# Connectors.net
KiCad netlist of a schematic drawn in Altium Designer
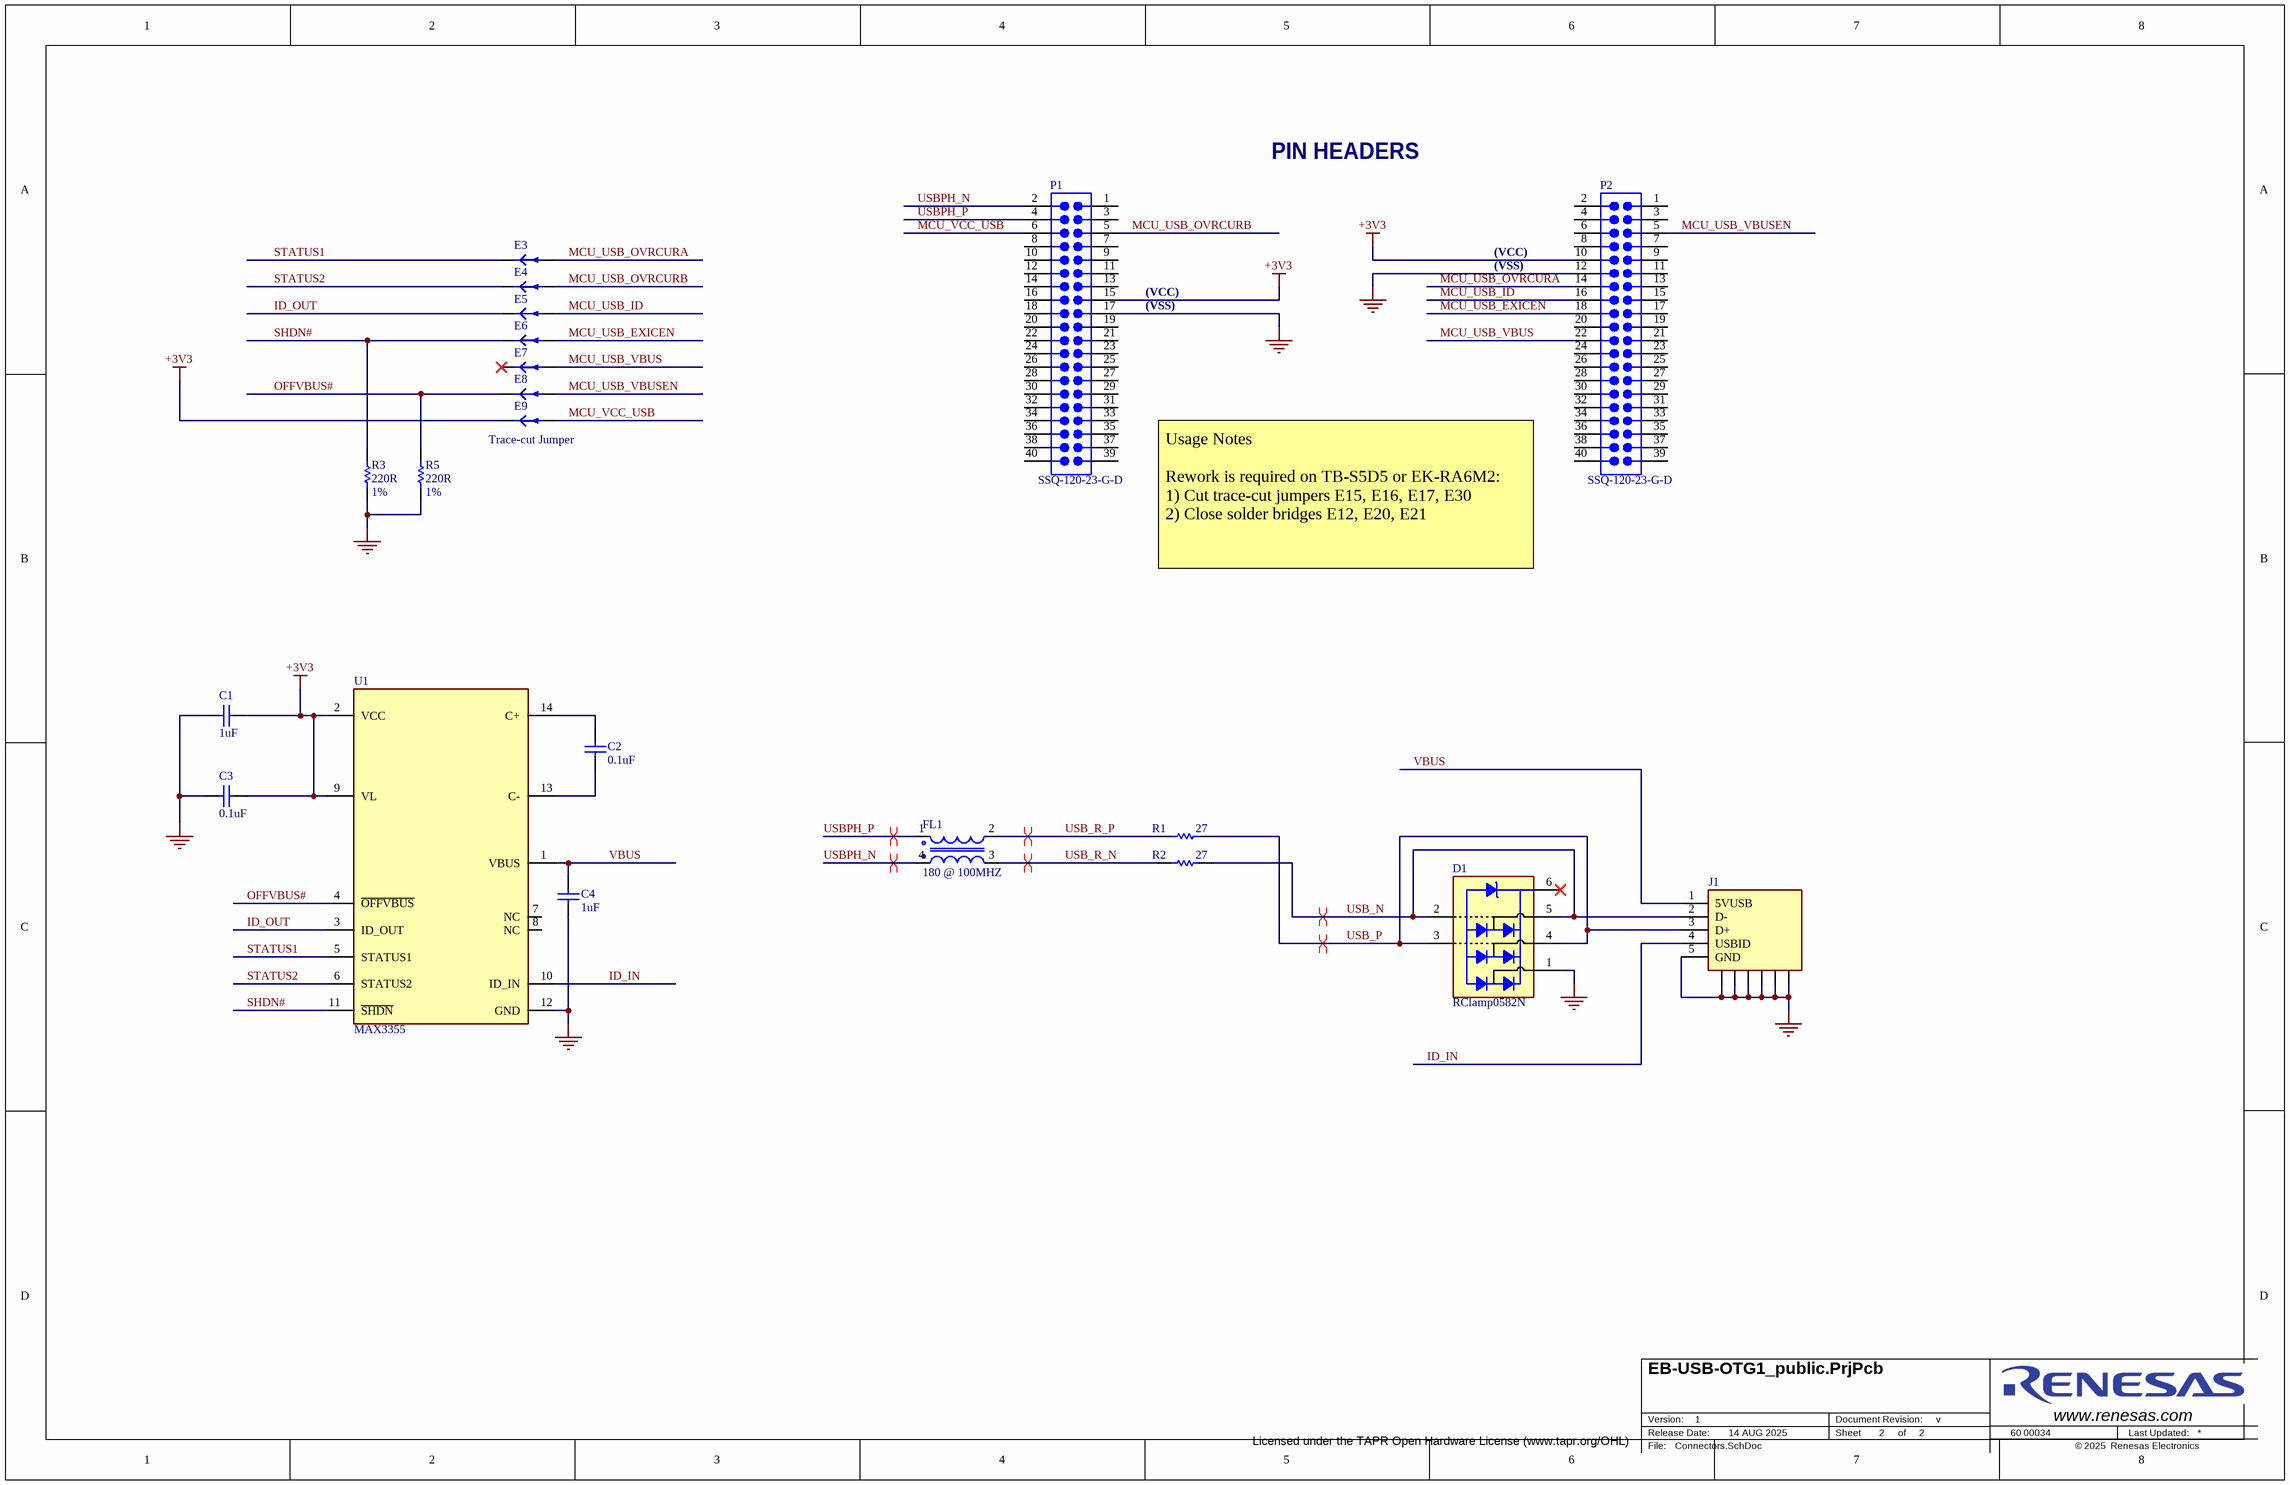
[diagram p0: Connectors.SchDoc]

(export (version "E")
  (design (tool "Eeschema 10.0.6"))
  (components
    (comp (ref "C1")
      (value "CAP-000074-01")
      (footprint "CAPC0603-01")
      (description "Ceramic Chip Capacitor 0603 1uF 50V")
      (fields
        (field (name "MANUFACTURER") "Taiyo Yuden")
        (field (name "MFG PART NUMBER") "UMK107BJ105KA-T")
        (field (name "CAPACITANCE") "1uF")
      )
      (libsource (lib "Capacitors") (part "CAP-000074-01"))
    )
    (comp (ref "C2")
      (value "CAP-000029-01")
      (footprint "CAPC0603-01")
      (description "Ceramic Chip Capacitor 0603 0.1uF 50V")
      (fields
        (field (name "MANUFACTURER") "Samsung")
        (field (name "MFG PART NUMBER") "CL10B104KB8NNNC")
        (field (name "CAPACITANCE") "0.1uF")
      )
      (libsource (lib "Capacitors") (part "CAP-000029-01"))
    )
    (comp (ref "C3")
      (value "CAP-000029-01")
      (footprint "CAPC0603-01")
      (description "Ceramic Chip Capacitor 0603 0.1uF 50V")
      (fields
        (field (name "MANUFACTURER") "Samsung")
        (field (name "MFG PART NUMBER") "CL10B104KB8NNNC")
        (field (name "CAPACITANCE") "0.1uF")
      )
      (libsource (lib "Capacitors") (part "CAP-000029-01"))
    )
    (comp (ref "C4")
      (value "CAP-000074-01")
      (footprint "CAPC0603-01")
      (description "Ceramic Chip Capacitor 0603 1uF 50V")
      (fields
        (field (name "MANUFACTURER") "Taiyo Yuden")
        (field (name "MFG PART NUMBER") "UMK107BJ105KA-T")
        (field (name "CAPACITANCE") "1uF")
      )
      (libsource (lib "Capacitors") (part "CAP-000074-01"))
    )
    (comp (ref "D1")
      (value "DIO-100005-01")
      (footprint "SEMTECH_SLP1210N6")
      (description "Semtech TVS Diode Array for USB")
      (fields
        (field (name "MANUFACTURER") "Semtech")
        (field (name "MFG PART NUMBER") "RClamp0582N.TCT")
        (field (name "DISPLAY NAME") "RClamp0582N")
      )
      (libsource (lib "Semiconductors") (part "DIO-100005-01"))
    )
    (comp (ref "E3")
      (value "TIE-100001-01")
      (footprint "TraceCut0805")
      (description "Trace-Cut Jumper.  Pads on PCB with Trace Between for Cutting to isolate")
      (libsource (lib "Misc") (part "TIE-100001-01"))
    )
    (comp (ref "E4")
      (value "TIE-100001-01")
      (footprint "TraceCut0805")
      (description "Trace-Cut Jumper.  Pads on PCB with Trace Between for Cutting to isolate")
      (libsource (lib "Misc") (part "TIE-100001-01"))
    )
    (comp (ref "E5")
      (value "TIE-100001-01")
      (footprint "TraceCut0805")
      (description "Trace-Cut Jumper.  Pads on PCB with Trace Between for Cutting to isolate")
      (libsource (lib "Misc") (part "TIE-100001-01"))
    )
    (comp (ref "E6")
      (value "TIE-100001-01")
      (footprint "TraceCut0805")
      (description "Trace-Cut Jumper.  Pads on PCB with Trace Between for Cutting to isolate")
      (libsource (lib "Misc") (part "TIE-100001-01"))
    )
    (comp (ref "E7")
      (value "TIE-100001-01")
      (footprint "TraceCut0805")
      (description "Trace-Cut Jumper.  Pads on PCB with Trace Between for Cutting to isolate")
      (libsource (lib "Misc") (part "TIE-100001-01"))
    )
    (comp (ref "E8")
      (value "TIE-100001-01")
      (footprint "TraceCut0805")
      (description "Trace-Cut Jumper.  Pads on PCB with Trace Between for Cutting to isolate")
      (libsource (lib "Misc") (part "TIE-100001-01"))
    )
    (comp (ref "E9")
      (value "TIE-100001-01")
      (footprint "TraceCut0805")
      (description "Trace-Cut Jumper.  Pads on PCB with Trace Between for Cutting to isolate")
      (fields (field (name "DISPLAY_NAME") "Trace-cut Jumper"))
      (libsource (lib "Misc") (part "TIE-100001-01"))
    )
    (comp (ref "FL1")
      (value "IND-100014-01")
      (footprint "MURATA_FL0805")
      (description "Common Mode Filter Inductor, 180 ohm CM @ 100MHz, 0805")
      (fields
        (field (name "MANUFACTURER") "Murata")
        (field (name "MFG PART NUMBER") "DLW21SN181SQ2")
        (field (name "RESISTANCE") "180 @ 100MHZ")
      )
      (libsource (lib "Misc") (part "IND-100014-01"))
    )
    (comp (ref "J1")
      (value "CON-100013-01")
      (footprint "MOLEX_47589-0001")
      (description "USB Micro AB 2.0 Female 5 Pin Right Angle Molex")
      (fields (field (name "MANUFACTURER") "Molex") (field (name "MFG PART NUMBER") "47589-0001"))
      (libsource (lib "Connectors") (part "CON-100013-01"))
    )
    (comp (ref "P1")
      (value "CON-100032-01")
      (footprint "SAMTEC_SSQ-120-23-x-D")
      (description "SAMTEC Female Header 0.1\" pitch 40pos 2x20, 10mm pins, gold flash tail")
      (fields
        (field (name "MANUFACTURER") "Samtec")
        (field (name "MFG PART NUMBER") "SSQ-120-23-G-D")
        (field (name "PN") "SSQ-120-23-G-D")
      )
      (libsource (lib "Connectors") (part "CON-100032-01"))
    )
    (comp (ref "P2")
      (value "CON-100032-01")
      (footprint "SAMTEC_SSQ-120-23-x-D")
      (description "SAMTEC Female Header 0.1\" pitch 40pos 2x20, 10mm pins, gold flash tail")
      (fields
        (field (name "MANUFACTURER") "Samtec")
        (field (name "MFG PART NUMBER") "SSQ-120-23-G-D")
        (field (name "PN") "SSQ-120-23-G-D")
      )
      (libsource (lib "Connectors") (part "CON-100032-01"))
    )
    (comp (ref "R1")
      (value "RES-100084-01")
      (footprint "RESC0603-01")
      (description "Chip Resistor Thick Film 0603 27R0 1% 1/10W")
      (fields
        (field (name "MANUFACTURER") "Yageo")
        (field (name "MFG PART NUMBER") "RC0603FR-0727RL")
        (field (name "RESISTANCE") "27")
      )
      (libsource (lib "Resistors") (part "RES-100084-01"))
    )
    (comp (ref "R2")
      (value "RES-100084-01")
      (footprint "RESC0603-01")
      (description "Chip Resistor Thick Film 0603 27R0 1% 1/10W")
      (fields
        (field (name "MANUFACTURER") "Yageo")
        (field (name "MFG PART NUMBER") "RC0603FR-0727RL")
        (field (name "RESISTANCE") "27")
      )
      (libsource (lib "Resistors") (part "RES-100084-01"))
    )
    (comp (ref "R3")
      (value "RES-100092-01")
      (footprint "RESC0603-01")
      (description "Chip Resistor Thick Film 0603 220 ohm 1% 1/10W")
      (fields
        (field (name "MANUFACTURER") "Yageo")
        (field (name "MFG PART NUMBER") "RC0603FR-07220RL")
        (field (name "RESISTANCE") "220R")
        (field (name "TOLERANCE") "1%")
      )
      (libsource (lib "Resistors") (part "RES-100092-01"))
    )
    (comp (ref "R5")
      (value "RES-100092-01")
      (footprint "RESC0603-01")
      (description "Chip Resistor Thick Film 0603 220 ohm 1% 1/10W")
      (fields
        (field (name "MANUFACTURER") "Yageo")
        (field (name "MFG PART NUMBER") "RC0603FR-07220RL")
        (field (name "RESISTANCE") "220R")
        (field (name "TOLERANCE") "1%")
      )
      (libsource (lib "Resistors") (part "RES-100092-01"))
    )
    (comp (ref "U1")
      (value "ICN-110015-01")
      (footprint "MAXIM_TSSOP-14")
      (description "USB OTG Charge Pump")
      (fields
        (field (name "MANUFACTURER") "Maxim")
        (field (name "MFG PART NUMBER") "MAX3355EEUD")
        (field (name "DISPLAY NAME") "MAX3355")
      )
      (libsource (lib "IC_Power") (part "ICN-110015-01"))
    )
  )
  (nets
    (net (code "1") (name "+3V3") (class "Default")
      (node (ref "C1") (pin "1") (pinfunction "1_1") (pintype "passive"))
      (node (ref "C3") (pin "1") (pinfunction "1_1") (pintype "passive"))
      (node (ref "E9") (pin "1") (pinfunction "A_1") (pintype "passive"))
      (node (ref "P1") (pin "15") (pinfunction "15_15") (pintype "passive"))
      (node (ref "P2") (pin "10") (pinfunction "10_10") (pintype "passive"))
      (node (ref "U1") (pin "2") (pinfunction "VCC_2") (pintype "power_in"))
      (node (ref "U1") (pin "9") (pinfunction "VL_9") (pintype "passive"))
    )
    (net (code "2") (name "/ID_IN") (class "Default")
      (node (ref "J1") (pin "4") (pinfunction "USBID_4") (pintype "passive"))
      (node (ref "U1") (pin "10") (pinfunction "ID_IN_10") (pintype "passive"))
    )
    (net (code "3") (name "/ID_OUT") (class "Default")
      (node (ref "E5") (pin "1") (pinfunction "A_1") (pintype "passive"))
      (node (ref "U1") (pin "3") (pinfunction "ID_OUT_3") (pintype "passive"))
    )
    (net (code "4") (name "/MCU_USB_EXICEN") (class "Default")
      (node (ref "E6") (pin "2") (pinfunction "A_2") (pintype "passive"))
      (node (ref "P2") (pin "18") (pinfunction "18_18") (pintype "passive"))
    )
    (net (code "5") (name "/MCU_USB_ID") (class "Default")
      (node (ref "E5") (pin "2") (pinfunction "A_2") (pintype "passive"))
      (node (ref "P2") (pin "16") (pinfunction "16_16") (pintype "passive"))
    )
    (net (code "6") (name "/MCU_USB_OVRCURA") (class "Default")
      (node (ref "E3") (pin "2") (pinfunction "A_2") (pintype "passive"))
      (node (ref "P2") (pin "14") (pinfunction "14_14") (pintype "passive"))
    )
    (net (code "7") (name "/MCU_USB_OVRCURB") (class "Default")
      (node (ref "E4") (pin "2") (pinfunction "A_2") (pintype "passive"))
      (node (ref "P1") (pin "5") (pinfunction "5_5") (pintype "passive"))
    )
    (net (code "8") (name "/MCU_USB_VBUS") (class "Default")
      (node (ref "E7") (pin "2") (pinfunction "A_2") (pintype "passive"))
      (node (ref "P2") (pin "22") (pinfunction "22_22") (pintype "passive"))
    )
    (net (code "9") (name "/MCU_USB_VBUSEN") (class "Default")
      (node (ref "E8") (pin "2") (pinfunction "A_2") (pintype "passive"))
      (node (ref "P2") (pin "5") (pinfunction "5_5") (pintype "passive"))
    )
    (net (code "10") (name "/MCU_VCC_USB") (class "Default")
      (node (ref "E9") (pin "2") (pinfunction "A_2") (pintype "passive"))
      (node (ref "P1") (pin "6") (pinfunction "6_6") (pintype "passive"))
    )
    (net (code "11") (name "/OFFVBUS#") (class "Default")
      (node (ref "E8") (pin "1") (pinfunction "A_1") (pintype "passive"))
      (node (ref "R5") (pin "2") (pinfunction "2_2") (pintype "passive"))
      (node (ref "U1") (pin "4") (pinfunction "~{OFFVBUS}_4") (pintype "power_in"))
    )
    (net (code "12") (name "/SHDN#") (class "Default")
      (node (ref "E6") (pin "1") (pinfunction "A_1") (pintype "passive"))
      (node (ref "R3") (pin "2") (pinfunction "2_2") (pintype "passive"))
      (node (ref "U1") (pin "11") (pinfunction "~{SHDN}_11") (pintype "passive"))
    )
    (net (code "13") (name "/STATUS1") (class "Default")
      (node (ref "E3") (pin "1") (pinfunction "A_1") (pintype "passive"))
      (node (ref "U1") (pin "5") (pinfunction "STATUS1_5") (pintype "passive"))
    )
    (net (code "14") (name "/STATUS2") (class "Default")
      (node (ref "E4") (pin "1") (pinfunction "A_1") (pintype "passive"))
      (node (ref "U1") (pin "6") (pinfunction "STATUS2_6") (pintype "passive"))
    )
    (net (code "15") (name "/USBPH_N") (class "Default")
      (node (ref "FL1") (pin "4") (pinfunction "4_4") (pintype "passive"))
      (node (ref "P1") (pin "2") (pinfunction "2_2") (pintype "passive"))
    )
    (net (code "16") (name "/USBPH_P") (class "Default")
      (node (ref "FL1") (pin "1") (pinfunction "1_1") (pintype "passive"))
      (node (ref "P1") (pin "4") (pinfunction "4_4") (pintype "passive"))
    )
    (net (code "17") (name "/USB_N") (class "Default")
      (node (ref "D1") (pin "2") (pinfunction "NC_2") (pintype "passive"))
      (node (ref "D1") (pin "5") (pinfunction "5_5") (pintype "passive"))
      (node (ref "J1") (pin "2") (pinfunction "D-_2") (pintype "passive"))
      (node (ref "R2") (pin "2") (pinfunction "2_2") (pintype "passive"))
    )
    (net (code "18") (name "/USB_P") (class "Default")
      (node (ref "D1") (pin "3") (pinfunction "NC_3") (pintype "passive"))
      (node (ref "D1") (pin "4") (pinfunction "4_4") (pintype "passive"))
      (node (ref "J1") (pin "3") (pinfunction "D+_3") (pintype "passive"))
      (node (ref "R1") (pin "2") (pinfunction "2_2") (pintype "passive"))
    )
    (net (code "19") (name "/USB_R_N") (class "Default")
      (node (ref "FL1") (pin "3") (pinfunction "3_3") (pintype "passive"))
      (node (ref "R2") (pin "1") (pinfunction "1_1") (pintype "passive"))
    )
    (net (code "20") (name "/USB_R_P") (class "Default")
      (node (ref "FL1") (pin "2") (pinfunction "2_2") (pintype "passive"))
      (node (ref "R1") (pin "1") (pinfunction "1_1") (pintype "passive"))
    )
    (net (code "21") (name "/VBUS") (class "Default")
      (node (ref "C4") (pin "2") (pinfunction "2_2") (pintype "passive"))
      (node (ref "J1") (pin "1") (pinfunction "5VUSB_1") (pintype "passive"))
      (node (ref "U1") (pin "1") (pinfunction "VBUS_1") (pintype "power_in"))
    )
    (net (code "22") (name "GND") (class "Default")
      (node (ref "C1") (pin "2") (pinfunction "2_2") (pintype "passive"))
      (node (ref "C3") (pin "2") (pinfunction "2_2") (pintype "passive"))
      (node (ref "C4") (pin "1") (pinfunction "1_1") (pintype "passive"))
      (node (ref "D1") (pin "1") (pinfunction "1_1") (pintype "passive"))
      (node (ref "J1") (pin "5") (pinfunction "GND_5") (pintype "passive"))
      (node (ref "J1") (pin "C1") (pinfunction "C1_C1") (pintype "passive"))
      (node (ref "J1") (pin "C2") (pinfunction "C2_C2") (pintype "passive"))
      (node (ref "J1") (pin "C3") (pinfunction "C3_C3") (pintype "passive"))
      (node (ref "J1") (pin "C4") (pinfunction "C4_C4") (pintype "passive"))
      (node (ref "J1") (pin "C5") (pinfunction "C5_C5") (pintype "passive"))
      (node (ref "J1") (pin "C6") (pinfunction "C6_C6") (pintype "passive"))
      (node (ref "P1") (pin "17") (pinfunction "17_17") (pintype "passive"))
      (node (ref "P2") (pin "12") (pinfunction "12_12") (pintype "passive"))
      (node (ref "R3") (pin "1") (pinfunction "1_1") (pintype "passive"))
      (node (ref "R5") (pin "1") (pinfunction "1_1") (pintype "passive"))
      (node (ref "U1") (pin "12") (pinfunction "GND_12") (pintype "passive"))
    )
    (net (code "23") (name "Net-(U1-C+)") (class "Default")
      (node (ref "C2") (pin "2") (pinfunction "2_2") (pintype "passive"))
      (node (ref "U1") (pin "14") (pinfunction "C+_14") (pintype "passive"))
    )
    (net (code "24") (name "Net-(U1-C-)") (class "Default")
      (node (ref "C2") (pin "1") (pinfunction "1_1") (pintype "passive"))
      (node (ref "U1") (pin "13") (pinfunction "C-_13") (pintype "passive"))
    )
    (net (code "25") (name "unconnected-(D1-Pad6)") (class "Default")
      (node (ref "D1") (pin "6") (pinfunction "6_6") (pintype "passive+no_connect"))
    )
    (net (code "26") (name "unconnected-(E7-A-Pad1)") (class "Default")
      (node (ref "E7") (pin "1") (pinfunction "A_1") (pintype "passive+no_connect"))
    )
    (net (code "27") (name "unconnected-(P1-Pad1)") (class "Default")
      (node (ref "P1") (pin "1") (pinfunction "1_1") (pintype "passive"))
    )
    (net (code "28") (name "unconnected-(P1-Pad3)") (class "Default")
      (node (ref "P1") (pin "3") (pinfunction "3_3") (pintype "passive"))
    )
    (net (code "29") (name "unconnected-(P1-Pad7)") (class "Default")
      (node (ref "P1") (pin "7") (pinfunction "7_7") (pintype "passive"))
    )
    (net (code "30") (name "unconnected-(P1-Pad8)") (class "Default")
      (node (ref "P1") (pin "8") (pinfunction "8_8") (pintype "passive"))
    )
    (net (code "31") (name "unconnected-(P1-Pad9)") (class "Default")
      (node (ref "P1") (pin "9") (pinfunction "9_9") (pintype "passive"))
    )
    (net (code "32") (name "unconnected-(P1-Pad10)") (class "Default")
      (node (ref "P1") (pin "10") (pinfunction "10_10") (pintype "passive"))
    )
    (net (code "33") (name "unconnected-(P1-Pad11)") (class "Default")
      (node (ref "P1") (pin "11") (pinfunction "11_11") (pintype "passive"))
    )
    (net (code "34") (name "unconnected-(P1-Pad12)") (class "Default")
      (node (ref "P1") (pin "12") (pinfunction "12_12") (pintype "passive"))
    )
    (net (code "35") (name "unconnected-(P1-Pad13)") (class "Default")
      (node (ref "P1") (pin "13") (pinfunction "13_13") (pintype "passive"))
    )
    (net (code "36") (name "unconnected-(P1-Pad14)") (class "Default")
      (node (ref "P1") (pin "14") (pinfunction "14_14") (pintype "passive"))
    )
    (net (code "37") (name "unconnected-(P1-Pad16)") (class "Default")
      (node (ref "P1") (pin "16") (pinfunction "16_16") (pintype "passive"))
    )
    (net (code "38") (name "unconnected-(P1-Pad18)") (class "Default")
      (node (ref "P1") (pin "18") (pinfunction "18_18") (pintype "passive"))
    )
    (net (code "39") (name "unconnected-(P1-Pad19)") (class "Default")
      (node (ref "P1") (pin "19") (pinfunction "19_19") (pintype "passive"))
    )
    (net (code "40") (name "unconnected-(P1-Pad20)") (class "Default")
      (node (ref "P1") (pin "20") (pinfunction "20_20") (pintype "passive"))
    )
    (net (code "41") (name "unconnected-(P1-Pad21)") (class "Default")
      (node (ref "P1") (pin "21") (pinfunction "21_21") (pintype "passive"))
    )
    (net (code "42") (name "unconnected-(P1-Pad22)") (class "Default")
      (node (ref "P1") (pin "22") (pinfunction "22_22") (pintype "passive"))
    )
    (net (code "43") (name "unconnected-(P1-Pad23)") (class "Default")
      (node (ref "P1") (pin "23") (pinfunction "23_23") (pintype "passive"))
    )
    (net (code "44") (name "unconnected-(P1-Pad24)") (class "Default")
      (node (ref "P1") (pin "24") (pinfunction "24_24") (pintype "passive"))
    )
    (net (code "45") (name "unconnected-(P1-Pad25)") (class "Default")
      (node (ref "P1") (pin "25") (pinfunction "25_25") (pintype "passive"))
    )
    (net (code "46") (name "unconnected-(P1-Pad26)") (class "Default")
      (node (ref "P1") (pin "26") (pinfunction "26_26") (pintype "passive"))
    )
    (net (code "47") (name "unconnected-(P1-Pad27)") (class "Default")
      (node (ref "P1") (pin "27") (pinfunction "27_27") (pintype "passive"))
    )
    (net (code "48") (name "unconnected-(P1-Pad28)") (class "Default")
      (node (ref "P1") (pin "28") (pinfunction "28_28") (pintype "passive"))
    )
    (net (code "49") (name "unconnected-(P1-Pad29)") (class "Default")
      (node (ref "P1") (pin "29") (pinfunction "29_29") (pintype "passive"))
    )
    (net (code "50") (name "unconnected-(P1-Pad30)") (class "Default")
      (node (ref "P1") (pin "30") (pinfunction "30_30") (pintype "passive"))
    )
    (net (code "51") (name "unconnected-(P1-Pad31)") (class "Default")
      (node (ref "P1") (pin "31") (pinfunction "31_31") (pintype "passive"))
    )
    (net (code "52") (name "unconnected-(P1-Pad32)") (class "Default")
      (node (ref "P1") (pin "32") (pinfunction "32_32") (pintype "passive"))
    )
    (net (code "53") (name "unconnected-(P1-Pad33)") (class "Default")
      (node (ref "P1") (pin "33") (pinfunction "33_33") (pintype "passive"))
    )
    (net (code "54") (name "unconnected-(P1-Pad34)") (class "Default")
      (node (ref "P1") (pin "34") (pinfunction "34_34") (pintype "passive"))
    )
    (net (code "55") (name "unconnected-(P1-Pad35)") (class "Default")
      (node (ref "P1") (pin "35") (pinfunction "35_35") (pintype "passive"))
    )
    (net (code "56") (name "unconnected-(P1-Pad36)") (class "Default")
      (node (ref "P1") (pin "36") (pinfunction "36_36") (pintype "passive"))
    )
    (net (code "57") (name "unconnected-(P1-Pad37)") (class "Default")
      (node (ref "P1") (pin "37") (pinfunction "37_37") (pintype "passive"))
    )
    (net (code "58") (name "unconnected-(P1-Pad38)") (class "Default")
      (node (ref "P1") (pin "38") (pinfunction "38_38") (pintype "passive"))
    )
    (net (code "59") (name "unconnected-(P1-Pad39)") (class "Default")
      (node (ref "P1") (pin "39") (pinfunction "39_39") (pintype "passive"))
    )
    (net (code "60") (name "unconnected-(P1-Pad40)") (class "Default")
      (node (ref "P1") (pin "40") (pinfunction "40_40") (pintype "passive"))
    )
    (net (code "61") (name "unconnected-(P2-Pad1)") (class "Default")
      (node (ref "P2") (pin "1") (pinfunction "1_1") (pintype "passive"))
    )
    (net (code "62") (name "unconnected-(P2-Pad2)") (class "Default")
      (node (ref "P2") (pin "2") (pinfunction "2_2") (pintype "passive"))
    )
    (net (code "63") (name "unconnected-(P2-Pad3)") (class "Default")
      (node (ref "P2") (pin "3") (pinfunction "3_3") (pintype "passive"))
    )
    (net (code "64") (name "unconnected-(P2-Pad4)") (class "Default")
      (node (ref "P2") (pin "4") (pinfunction "4_4") (pintype "passive"))
    )
    (net (code "65") (name "unconnected-(P2-Pad6)") (class "Default")
      (node (ref "P2") (pin "6") (pinfunction "6_6") (pintype "passive"))
    )
    (net (code "66") (name "unconnected-(P2-Pad7)") (class "Default")
      (node (ref "P2") (pin "7") (pinfunction "7_7") (pintype "passive"))
    )
    (net (code "67") (name "unconnected-(P2-Pad8)") (class "Default")
      (node (ref "P2") (pin "8") (pinfunction "8_8") (pintype "passive"))
    )
    (net (code "68") (name "unconnected-(P2-Pad9)") (class "Default")
      (node (ref "P2") (pin "9") (pinfunction "9_9") (pintype "passive"))
    )
    (net (code "69") (name "unconnected-(P2-Pad11)") (class "Default")
      (node (ref "P2") (pin "11") (pinfunction "11_11") (pintype "passive"))
    )
    (net (code "70") (name "unconnected-(P2-Pad13)") (class "Default")
      (node (ref "P2") (pin "13") (pinfunction "13_13") (pintype "passive"))
    )
    (net (code "71") (name "unconnected-(P2-Pad15)") (class "Default")
      (node (ref "P2") (pin "15") (pinfunction "15_15") (pintype "passive"))
    )
    (net (code "72") (name "unconnected-(P2-Pad17)") (class "Default")
      (node (ref "P2") (pin "17") (pinfunction "17_17") (pintype "passive"))
    )
    (net (code "73") (name "unconnected-(P2-Pad19)") (class "Default")
      (node (ref "P2") (pin "19") (pinfunction "19_19") (pintype "passive"))
    )
    (net (code "74") (name "unconnected-(P2-Pad20)") (class "Default")
      (node (ref "P2") (pin "20") (pinfunction "20_20") (pintype "passive"))
    )
    (net (code "75") (name "unconnected-(P2-Pad21)") (class "Default")
      (node (ref "P2") (pin "21") (pinfunction "21_21") (pintype "passive"))
    )
    (net (code "76") (name "unconnected-(P2-Pad23)") (class "Default")
      (node (ref "P2") (pin "23") (pinfunction "23_23") (pintype "passive"))
    )
    (net (code "77") (name "unconnected-(P2-Pad24)") (class "Default")
      (node (ref "P2") (pin "24") (pinfunction "24_24") (pintype "passive"))
    )
    (net (code "78") (name "unconnected-(P2-Pad25)") (class "Default")
      (node (ref "P2") (pin "25") (pinfunction "25_25") (pintype "passive"))
    )
    (net (code "79") (name "unconnected-(P2-Pad26)") (class "Default")
      (node (ref "P2") (pin "26") (pinfunction "26_26") (pintype "passive"))
    )
    (net (code "80") (name "unconnected-(P2-Pad27)") (class "Default")
      (node (ref "P2") (pin "27") (pinfunction "27_27") (pintype "passive"))
    )
    (net (code "81") (name "unconnected-(P2-Pad28)") (class "Default")
      (node (ref "P2") (pin "28") (pinfunction "28_28") (pintype "passive"))
    )
    (net (code "82") (name "unconnected-(P2-Pad29)") (class "Default")
      (node (ref "P2") (pin "29") (pinfunction "29_29") (pintype "passive"))
    )
    (net (code "83") (name "unconnected-(P2-Pad30)") (class "Default")
      (node (ref "P2") (pin "30") (pinfunction "30_30") (pintype "passive"))
    )
    (net (code "84") (name "unconnected-(P2-Pad31)") (class "Default")
      (node (ref "P2") (pin "31") (pinfunction "31_31") (pintype "passive"))
    )
    (net (code "85") (name "unconnected-(P2-Pad32)") (class "Default")
      (node (ref "P2") (pin "32") (pinfunction "32_32") (pintype "passive"))
    )
    (net (code "86") (name "unconnected-(P2-Pad33)") (class "Default")
      (node (ref "P2") (pin "33") (pinfunction "33_33") (pintype "passive"))
    )
    (net (code "87") (name "unconnected-(P2-Pad34)") (class "Default")
      (node (ref "P2") (pin "34") (pinfunction "34_34") (pintype "passive"))
    )
    (net (code "88") (name "unconnected-(P2-Pad35)") (class "Default")
      (node (ref "P2") (pin "35") (pinfunction "35_35") (pintype "passive"))
    )
    (net (code "89") (name "unconnected-(P2-Pad36)") (class "Default")
      (node (ref "P2") (pin "36") (pinfunction "36_36") (pintype "passive"))
    )
    (net (code "90") (name "unconnected-(P2-Pad37)") (class "Default")
      (node (ref "P2") (pin "37") (pinfunction "37_37") (pintype "passive"))
    )
    (net (code "91") (name "unconnected-(P2-Pad38)") (class "Default")
      (node (ref "P2") (pin "38") (pinfunction "38_38") (pintype "passive"))
    )
    (net (code "92") (name "unconnected-(P2-Pad39)") (class "Default")
      (node (ref "P2") (pin "39") (pinfunction "39_39") (pintype "passive"))
    )
    (net (code "93") (name "unconnected-(P2-Pad40)") (class "Default")
      (node (ref "P2") (pin "40") (pinfunction "40_40") (pintype "passive"))
    )
    (net (code "94") (name "unconnected-(U1-NC-Pad7)") (class "Default")
      (node (ref "U1") (pin "7") (pinfunction "NC_7") (pintype "passive"))
    )
    (net (code "95") (name "unconnected-(U1-NC-Pad8)") (class "Default")
      (node (ref "U1") (pin "8") (pinfunction "NC_8") (pintype "passive"))
    )
  )
)
